# Beepoo.net
KiCad netlist of a schematic drawn in EAGLE
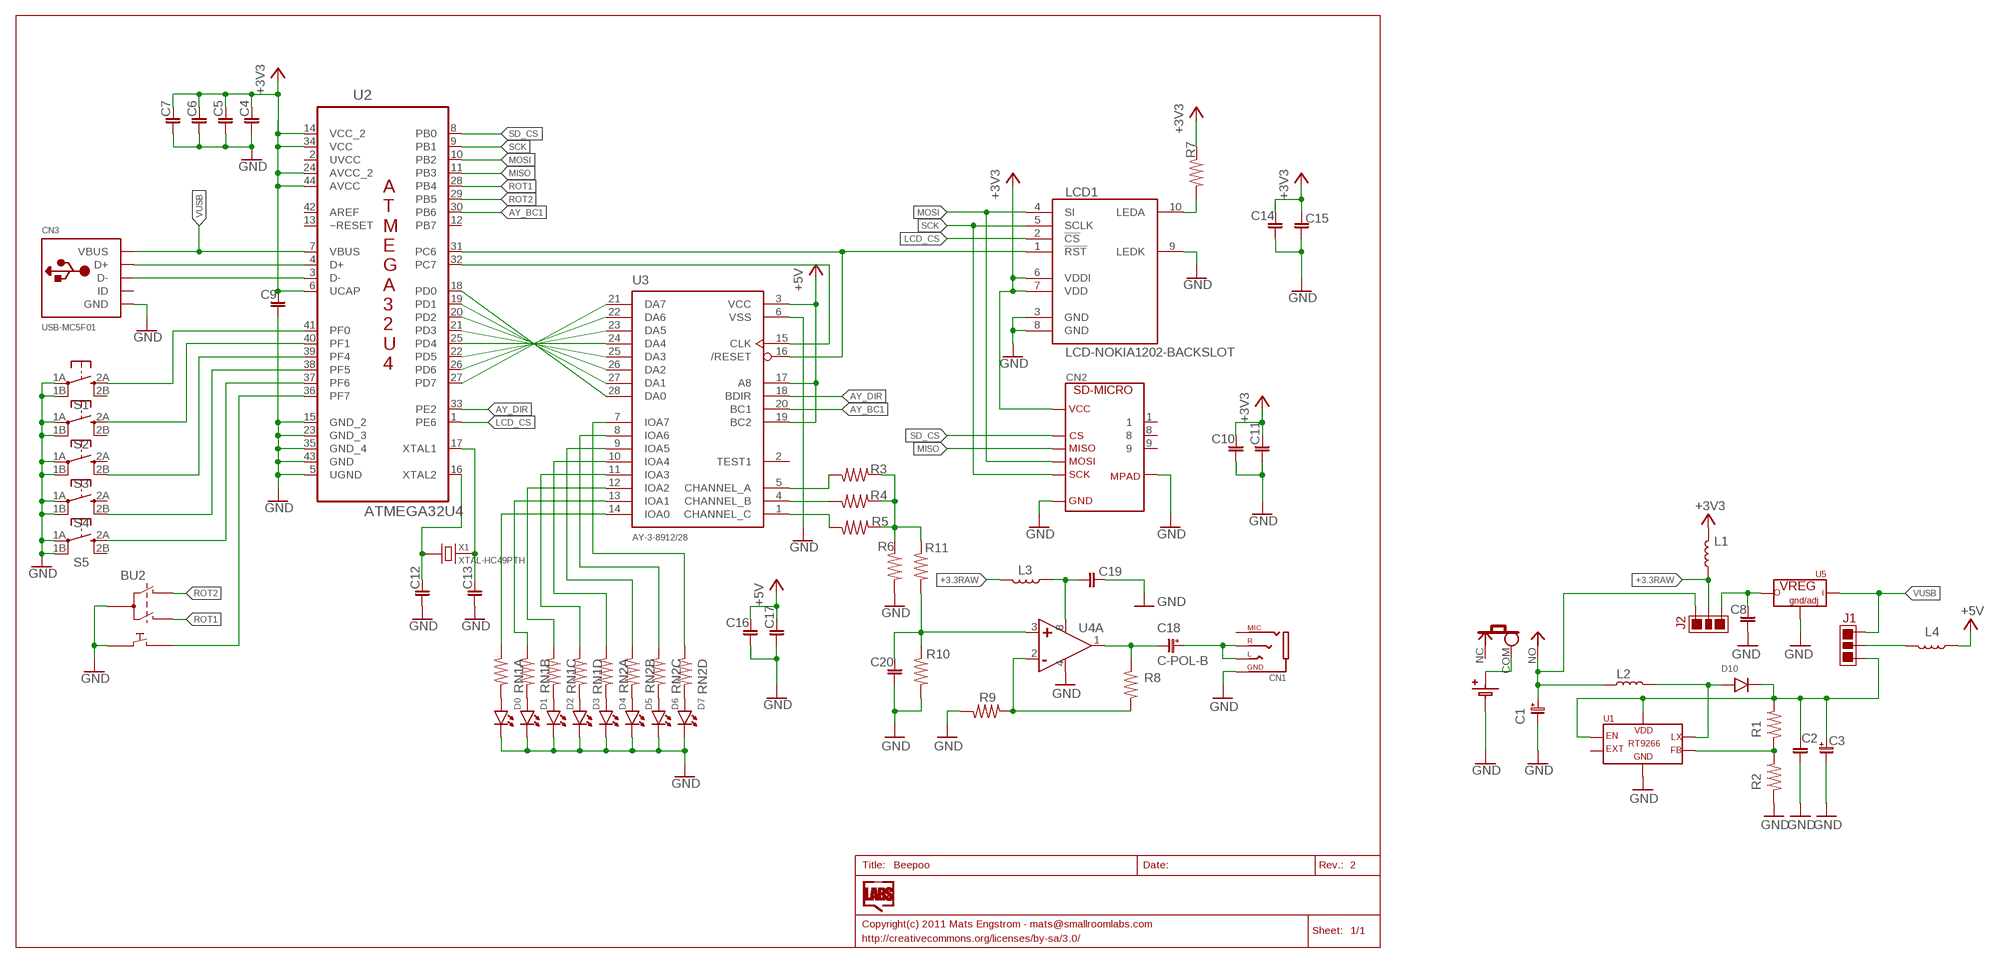
[diagram p0: schematic, sheet 1]

(export (version "E")
  (design (tool "Eeschema 10.0.6"))
  (components
    (comp (ref "BA1")
      (value "BATTERY2-CR123")
      (footprint "eagle-import:BAT-CR123A")
      (libsource (lib "eagle-import") (part "BATTERY2-CR123"))
    )
    (comp (ref "BU2")
      (value "ROTARY")
      (footprint "eagle-import:ROTARY")
      (libsource (lib "eagle-import") (part "ROTARY"))
    )
    (comp (ref "C1")
      (value "C-POL-C")
      (footprint "eagle-import:PANASONIC_C")
      (libsource (lib "eagle-import") (part "C-POL-C"))
    )
    (comp (ref "C2")
      (value "C-0805")
      (footprint "eagle-import:C0805")
      (libsource (lib "eagle-import") (part "C-0805"))
    )
    (comp (ref "C3")
      (value "EEEFK0J101UR")
      (footprint "eagle-import:PANASONIC_C")
      (libsource (lib "eagle-import") (part "C-POL-C"))
    )
    (comp (ref "C4")
      (value "C-0805")
      (footprint "eagle-import:C0805")
      (libsource (lib "eagle-import") (part "C-0805"))
    )
    (comp (ref "C5")
      (value "C-0805")
      (footprint "eagle-import:C0805")
      (libsource (lib "eagle-import") (part "C-0805"))
    )
    (comp (ref "C6")
      (value "C-0805")
      (footprint "eagle-import:C0805")
      (libsource (lib "eagle-import") (part "C-0805"))
    )
    (comp (ref "C7")
      (value "C-0805")
      (footprint "eagle-import:C0805")
      (libsource (lib "eagle-import") (part "C-0805"))
    )
    (comp (ref "C8")
      (value "1u")
      (footprint "eagle-import:C0805")
      (libsource (lib "eagle-import") (part "C-0805"))
    )
    (comp (ref "C9")
      (value "1u")
      (footprint "eagle-import:C0805")
      (libsource (lib "eagle-import") (part "C-0805"))
    )
    (comp (ref "C10")
      (value "1u")
      (footprint "eagle-import:C0805")
      (libsource (lib "eagle-import") (part "C-0805"))
    )
    (comp (ref "C11")
      (value "C-0805")
      (footprint "eagle-import:C0805")
      (libsource (lib "eagle-import") (part "C-0805"))
    )
    (comp (ref "C12")
      (value "C-0805")
      (footprint "eagle-import:C0805")
      (libsource (lib "eagle-import") (part "C-0805"))
    )
    (comp (ref "C13")
      (value "C-0805")
      (footprint "eagle-import:C0805")
      (libsource (lib "eagle-import") (part "C-0805"))
    )
    (comp (ref "C14")
      (value "1u")
      (footprint "eagle-import:C0805")
      (libsource (lib "eagle-import") (part "C-0805"))
    )
    (comp (ref "C15")
      (value "C-0805")
      (footprint "eagle-import:C0805")
      (libsource (lib "eagle-import") (part "C-0805"))
    )
    (comp (ref "C16")
      (value "1u")
      (footprint "eagle-import:C0805")
      (libsource (lib "eagle-import") (part "C-0805"))
    )
    (comp (ref "C17")
      (value "C-0805")
      (footprint "eagle-import:C0805")
      (libsource (lib "eagle-import") (part "C-0805"))
    )
    (comp (ref "C18")
      (value "C-POL-B")
      (footprint "eagle-import:PANASONIC_B")
      (libsource (lib "eagle-import") (part "C-POL-B"))
    )
    (comp (ref "C19")
      (value "1u")
      (footprint "eagle-import:C0805")
      (libsource (lib "eagle-import") (part "C-0805"))
    )
    (comp (ref "C20")
      (value "C-0805")
      (footprint "eagle-import:C0805")
      (libsource (lib "eagle-import") (part "C-0805"))
    )
    (comp (ref "CN1")
      (value "JACK4PTH")
      (footprint "eagle-import:PJ320E")
      (libsource (lib "eagle-import") (part "JACK4PTH"))
    )
    (comp (ref "CN2")
      (value "SD-MICRO")
      (footprint "eagle-import:SD-TFP09")
      (libsource (lib "eagle-import") (part "SD-MICRO"))
    )
    (comp (ref "CN3")
      (value "USB-MC5F01")
      (footprint "eagle-import:USB-MICRO-MC5F01")
      (libsource (lib "eagle-import") (part "USB-MC5F01"))
    )
    (comp (ref "D0")
      (value "LED-0805")
      (footprint "eagle-import:LED0805")
      (libsource (lib "eagle-import") (part "LED-0805"))
    )
    (comp (ref "D1")
      (value "LED-0805")
      (footprint "eagle-import:LED0805")
      (libsource (lib "eagle-import") (part "LED-0805"))
    )
    (comp (ref "D2")
      (value "LED-0805")
      (footprint "eagle-import:LED0805")
      (libsource (lib "eagle-import") (part "LED-0805"))
    )
    (comp (ref "D3")
      (value "LED-0805")
      (footprint "eagle-import:LED0805")
      (libsource (lib "eagle-import") (part "LED-0805"))
    )
    (comp (ref "D4")
      (value "LED-0805")
      (footprint "eagle-import:LED0805")
      (libsource (lib "eagle-import") (part "LED-0805"))
    )
    (comp (ref "D5")
      (value "LED-0805")
      (footprint "eagle-import:LED0805")
      (libsource (lib "eagle-import") (part "LED-0805"))
    )
    (comp (ref "D6")
      (value "LED-0805")
      (footprint "eagle-import:LED0805")
      (libsource (lib "eagle-import") (part "LED-0805"))
    )
    (comp (ref "D7")
      (value "LED-0805")
      (footprint "eagle-import:LED0805")
      (libsource (lib "eagle-import") (part "LED-0805"))
    )
    (comp (ref "D10")
      (value "DIODE-SOD123")
      (footprint "eagle-import:SOD123")
      (libsource (lib "eagle-import") (part "DIODE-SOD123"))
    )
    (comp (ref "J1")
      (value "JUMPER3-1.5MM")
      (footprint "eagle-import:JP3-1.5MM")
      (libsource (lib "eagle-import") (part "JUMPER3-1.5MM"))
    )
    (comp (ref "J2")
      (value "JUMPER3-1.5MM")
      (footprint "eagle-import:JP3-1.5MM")
      (libsource (lib "eagle-import") (part "JUMPER3-1.5MM"))
    )
    (comp (ref "L1")
      (value "L-0805")
      (footprint "eagle-import:L0805")
      (libsource (lib "eagle-import") (part "L-0805"))
    )
    (comp (ref "L2")
      (value "L-BOURNS-SRP7030")
      (footprint "eagle-import:IND-BOURNS-SRP7030")
      (libsource (lib "eagle-import") (part "L-BOURNS-SRP7030"))
    )
    (comp (ref "L3")
      (value "L-0805")
      (footprint "eagle-import:L0805")
      (libsource (lib "eagle-import") (part "L-0805"))
    )
    (comp (ref "L4")
      (value "L-0805")
      (footprint "eagle-import:L0805")
      (libsource (lib "eagle-import") (part "L-0805"))
    )
    (comp (ref "LCD1")
      (value "LCD-NOKIA1202-BACKSLOT")
      (footprint "eagle-import:NOKIA1202LCD-BACK-SLOT")
      (libsource (lib "eagle-import") (part "LCD-NOKIA1202-BACKSLOT"))
    )
    (comp (ref "R1")
      (value "R-0805")
      (footprint "eagle-import:R0805")
      (libsource (lib "eagle-import") (part "R-0805"))
    )
    (comp (ref "R2")
      (value "R-0805")
      (footprint "eagle-import:R0805")
      (libsource (lib "eagle-import") (part "R-0805"))
    )
    (comp (ref "R3")
      (value "R-0805")
      (footprint "eagle-import:R0805")
      (libsource (lib "eagle-import") (part "R-0805"))
    )
    (comp (ref "R4")
      (value "R-0805")
      (footprint "eagle-import:R0805")
      (libsource (lib "eagle-import") (part "R-0805"))
    )
    (comp (ref "R5")
      (value "R-0805")
      (footprint "eagle-import:R0805")
      (libsource (lib "eagle-import") (part "R-0805"))
    )
    (comp (ref "R6")
      (value "R-0805")
      (footprint "eagle-import:R0805")
      (libsource (lib "eagle-import") (part "R-0805"))
    )
    (comp (ref "R7")
      (value "R-0805")
      (footprint "eagle-import:R0805")
      (libsource (lib "eagle-import") (part "R-0805"))
    )
    (comp (ref "R8")
      (value "R-0805")
      (footprint "eagle-import:R0805")
      (libsource (lib "eagle-import") (part "R-0805"))
    )
    (comp (ref "R9")
      (value "R-0805")
      (footprint "eagle-import:R0805")
      (libsource (lib "eagle-import") (part "R-0805"))
    )
    (comp (ref "R10")
      (value "R-0805")
      (footprint "eagle-import:R0805")
      (libsource (lib "eagle-import") (part "R-0805"))
    )
    (comp (ref "R11")
      (value "R-0805")
      (footprint "eagle-import:R0805")
      (libsource (lib "eagle-import") (part "R-0805"))
    )
    (comp (ref "RN1")
      (value "R-ARR4")
      (footprint "eagle-import:RN8P-4R-CRA06S")
      (libsource (lib "eagle-import") (part "R-ARR4"))
    )
    (comp (ref "RN2")
      (value "R-ARR4")
      (footprint "eagle-import:RN8P-4R-CRA06S")
      (libsource (lib "eagle-import") (part "R-ARR4"))
    )
    (comp (ref "S1")
      (value "SWITCH2-12X12PTH")
      (footprint "eagle-import:TACT12X12-PTH")
      (libsource (lib "eagle-import") (part "SWITCH2-12X12PTH"))
    )
    (comp (ref "S2")
      (value "SWITCH2-12X12PTH")
      (footprint "eagle-import:TACT12X12-PTH")
      (libsource (lib "eagle-import") (part "SWITCH2-12X12PTH"))
    )
    (comp (ref "S3")
      (value "SWITCH2-12X12PTH")
      (footprint "eagle-import:TACT12X12-PTH")
      (libsource (lib "eagle-import") (part "SWITCH2-12X12PTH"))
    )
    (comp (ref "S4")
      (value "SWITCH2-12X12PTH")
      (footprint "eagle-import:TACT12X12-PTH")
      (libsource (lib "eagle-import") (part "SWITCH2-12X12PTH"))
    )
    (comp (ref "S5")
      (value "SWITCH2-12X12PTH")
      (footprint "eagle-import:TACT12X12-PTH")
      (libsource (lib "eagle-import") (part "SWITCH2-12X12PTH"))
    )
    (comp (ref "SW2")
      (value "SLIDE1-PCM12")
      (footprint "eagle-import:SW-PCM12")
      (libsource (lib "eagle-import") (part "SLIDE1-PCM12"))
    )
    (comp (ref "U1")
      (value "RT9266-SOT23")
      (footprint "eagle-import:SOT23-6")
      (libsource (lib "eagle-import") (part "RT9266-SOT23"))
    )
    (comp (ref "U2")
      (value "ATMEGA32U4")
      (footprint "eagle-import:TQFP44")
      (libsource (lib "eagle-import") (part "ATMEGA32U4"))
    )
    (comp (ref "U3")
      (value "AY-3-8912/28")
      (footprint "eagle-import:DIL28-6")
      (libsource (lib "eagle-import") (part "AY-3-8912/28"))
    )
    (comp (ref "U4")
      (value "OPAMP-DUAL-SOIC8")
      (footprint "eagle-import:SO08")
      (libsource (lib "eagle-import") (part "OPAMP-DUAL-SOIC8"))
    )
    (comp (ref "U5")
      (value "VREG3-SOT223")
      (footprint "eagle-import:SOT223")
      (libsource (lib "eagle-import") (part "VREG3-SOT223"))
    )
    (comp (ref "X1")
      (value "XTAL-HC49PTH")
      (footprint "eagle-import:HC49US")
      (libsource (lib "eagle-import") (part "XTAL-HC49PTH"))
    )
  )
  (nets
    (net (code "1") (name "+3.3RAW") (class "Default")
      (node (ref "J2") (pin "P$2") (pinfunction "P$2_P$2") (pintype "bidirectional"))
      (node (ref "L1") (pin "1") (pinfunction "P$1_1") (pintype "bidirectional"))
      (node (ref "L3") (pin "2") (pinfunction "P$2_2") (pintype "bidirectional"))
    )
    (net (code "2") (name "+3V3") (class "Default")
      (node (ref "C10") (pin "2") (pinfunction "P$2_2") (pintype "bidirectional"))
      (node (ref "C11") (pin "2") (pinfunction "P$2_2") (pintype "bidirectional"))
      (node (ref "C14") (pin "2") (pinfunction "P$2_2") (pintype "bidirectional"))
      (node (ref "C15") (pin "2") (pinfunction "P$2_2") (pintype "bidirectional"))
      (node (ref "C4") (pin "2") (pinfunction "P$2_2") (pintype "bidirectional"))
      (node (ref "C5") (pin "2") (pinfunction "P$2_2") (pintype "bidirectional"))
      (node (ref "C6") (pin "2") (pinfunction "P$2_2") (pintype "bidirectional"))
      (node (ref "C7") (pin "2") (pinfunction "P$2_2") (pintype "bidirectional"))
      (node (ref "C9") (pin "2") (pinfunction "P$2_2") (pintype "bidirectional"))
      (node (ref "CN2") (pin "4") (pinfunction "P$4_4") (pintype "power_in"))
      (node (ref "L1") (pin "2") (pinfunction "P$2_2") (pintype "bidirectional"))
      (node (ref "LCD1") (pin "6") (pinfunction "VDDI_6") (pintype "power_in"))
      (node (ref "LCD1") (pin "7") (pinfunction "VDD_7") (pintype "power_in"))
      (node (ref "R7") (pin "1") (pinfunction "P$1_1") (pintype "passive"))
      (node (ref "U2") (pin "14") (pinfunction "VCC_2_14") (pintype "power_in"))
      (node (ref "U2") (pin "24") (pinfunction "AVCC_2_24") (pintype "power_in"))
      (node (ref "U2") (pin "34") (pinfunction "VCC_34") (pintype "power_in"))
      (node (ref "U2") (pin "44") (pinfunction "AVCC_44") (pintype "power_in"))
      (node (ref "U2") (pin "6") (pinfunction "UCAP_6") (pintype "power_in"))
    )
    (net (code "3") (name "+5V") (class "Default")
      (node (ref "C16") (pin "2") (pinfunction "P$2_2") (pintype "bidirectional"))
      (node (ref "C17") (pin "2") (pinfunction "P$2_2") (pintype "bidirectional"))
      (node (ref "L4") (pin "1") (pinfunction "P$1_1") (pintype "bidirectional"))
      (node (ref "U3") (pin "17") (pinfunction "A8_17") (pintype "input"))
      (node (ref "U3") (pin "19") (pinfunction "BC2_19") (pintype "input"))
      (node (ref "U3") (pin "3") (pinfunction "VCC_3") (pintype "power_in"))
    )
    (net (code "4") (name "/UVCC") (class "Default")
      (node (ref "U2") (pin "2") (pinfunction "UVCC_2") (pintype "power_in"))
    )
    (net (code "5") (name "AY_BC1") (class "Default")
      (node (ref "U2") (pin "30") (pinfunction "PB6_30") (pintype "bidirectional"))
      (node (ref "U3") (pin "20") (pinfunction "BC1_20") (pintype "input"))
    )
    (net (code "6") (name "AY_DIR") (class "Default")
      (node (ref "U2") (pin "33") (pinfunction "PE2_33") (pintype "bidirectional"))
      (node (ref "U3") (pin "18") (pinfunction "BDIR_18") (pintype "input"))
    )
    (net (code "7") (name "GND") (class "Default")
      (node (ref "BA1") (pin "NEG") (pinfunction "NEG_NEG") (pintype "power_in"))
      (node (ref "BU2") (pin "Q") (pinfunction "Q_Q") (pintype "bidirectional"))
      (node (ref "BU2") (pin "SW1") (pinfunction "SW1_SW1") (pintype "bidirectional"))
      (node (ref "C1") (pin "-") (pinfunction "C_-") (pintype "bidirectional"))
      (node (ref "C10") (pin "1") (pinfunction "P$1_1") (pintype "bidirectional"))
      (node (ref "C11") (pin "1") (pinfunction "P$1_1") (pintype "bidirectional"))
      (node (ref "C12") (pin "1") (pinfunction "P$1_1") (pintype "bidirectional"))
      (node (ref "C13") (pin "1") (pinfunction "P$1_1") (pintype "bidirectional"))
      (node (ref "C14") (pin "1") (pinfunction "P$1_1") (pintype "bidirectional"))
      (node (ref "C15") (pin "1") (pinfunction "P$1_1") (pintype "bidirectional"))
      (node (ref "C16") (pin "1") (pinfunction "P$1_1") (pintype "bidirectional"))
      (node (ref "C17") (pin "1") (pinfunction "P$1_1") (pintype "bidirectional"))
      (node (ref "C19") (pin "2") (pinfunction "P$2_2") (pintype "bidirectional"))
      (node (ref "C2") (pin "2") (pinfunction "P$2_2") (pintype "bidirectional"))
      (node (ref "C20") (pin "1") (pinfunction "P$1_1") (pintype "bidirectional"))
      (node (ref "C3") (pin "-") (pinfunction "C_-") (pintype "bidirectional"))
      (node (ref "C4") (pin "1") (pinfunction "P$1_1") (pintype "bidirectional"))
      (node (ref "C5") (pin "1") (pinfunction "P$1_1") (pintype "bidirectional"))
      (node (ref "C6") (pin "1") (pinfunction "P$1_1") (pintype "bidirectional"))
      (node (ref "C7") (pin "1") (pinfunction "P$1_1") (pintype "bidirectional"))
      (node (ref "C8") (pin "1") (pinfunction "P$1_1") (pintype "bidirectional"))
      (node (ref "C9") (pin "1") (pinfunction "P$1_1") (pintype "bidirectional"))
      (node (ref "CN1") (pin "G") (pinfunction "GND_G") (pintype "bidirectional"))
      (node (ref "CN2") (pin "GND@1") (pinfunction "P$6_GND@1") (pintype "power_in"))
      (node (ref "CN2") (pin "GND@2") (pinfunction "P$10_GND@2") (pintype "bidirectional"))
      (node (ref "CN3") (pin "P5") (pinfunction "GND_P5") (pintype "power_in"))
      (node (ref "D0") (pin "C") (pinfunction "C_C") (pintype "passive"))
      (node (ref "D1") (pin "C") (pinfunction "C_C") (pintype "passive"))
      (node (ref "D2") (pin "C") (pinfunction "C_C") (pintype "passive"))
      (node (ref "D3") (pin "C") (pinfunction "C_C") (pintype "passive"))
      (node (ref "D4") (pin "C") (pinfunction "C_C") (pintype "passive"))
      (node (ref "D5") (pin "C") (pinfunction "C_C") (pintype "passive"))
      (node (ref "D6") (pin "C") (pinfunction "C_C") (pintype "passive"))
      (node (ref "D7") (pin "C") (pinfunction "C_C") (pintype "passive"))
      (node (ref "LCD1") (pin "3") (pinfunction "GND_3") (pintype "power_in"))
      (node (ref "LCD1") (pin "8") (pinfunction "GND_8") (pintype "power_in"))
      (node (ref "LCD1") (pin "9") (pinfunction "LEDK_9") (pintype "passive"))
      (node (ref "R10") (pin "2") (pinfunction "P$2_2") (pintype "passive"))
      (node (ref "R2") (pin "1") (pinfunction "P$1_1") (pintype "passive"))
      (node (ref "R6") (pin "2") (pinfunction "P$2_2") (pintype "passive"))
      (node (ref "R9") (pin "2") (pinfunction "P$2_2") (pintype "passive"))
      (node (ref "S1") (pin "1A") (pinfunction "1A_1A") (pintype "passive"))
      (node (ref "S1") (pin "1B") (pinfunction "1B_1B") (pintype "passive"))
      (node (ref "S2") (pin "1A") (pinfunction "1A_1A") (pintype "passive"))
      (node (ref "S2") (pin "1B") (pinfunction "1B_1B") (pintype "passive"))
      (node (ref "S3") (pin "1A") (pinfunction "1A_1A") (pintype "passive"))
      (node (ref "S3") (pin "1B") (pinfunction "1B_1B") (pintype "passive"))
      (node (ref "S4") (pin "1A") (pinfunction "1A_1A") (pintype "passive"))
      (node (ref "S4") (pin "1B") (pinfunction "1B_1B") (pintype "passive"))
      (node (ref "S5") (pin "1A") (pinfunction "1A_1A") (pintype "passive"))
      (node (ref "S5") (pin "1B") (pinfunction "1B_1B") (pintype "passive"))
      (node (ref "U1") (pin "3") (pinfunction "GND_3") (pintype "power_in"))
      (node (ref "U2") (pin "15") (pinfunction "GND_2_15") (pintype "passive"))
      (node (ref "U2") (pin "23") (pinfunction "GND_3_23") (pintype "passive"))
      (node (ref "U2") (pin "35") (pinfunction "GND_4_35") (pintype "passive"))
      (node (ref "U2") (pin "43") (pinfunction "GND_43") (pintype "passive"))
      (node (ref "U2") (pin "5") (pinfunction "UGND_5") (pintype "passive"))
      (node (ref "U3") (pin "6") (pinfunction "VSS_6") (pintype "power_in"))
      (node (ref "U4") (pin "4") (pinfunction "V-_4") (pintype "power_in"))
      (node (ref "U5") (pin "1") (pinfunction "G/A_1") (pintype "bidirectional"))
    )
    (net (code "8") (name "LCD_CS") (class "Default")
      (node (ref "LCD1") (pin "2") (pinfunction "~{CS}_2") (pintype "input"))
      (node (ref "U2") (pin "1") (pinfunction "PE6_1") (pintype "bidirectional"))
    )
    (net (code "9") (name "MISO") (class "Default")
      (node (ref "CN2") (pin "7") (pinfunction "P$7_7") (pintype "output"))
      (node (ref "U2") (pin "11") (pinfunction "PB3_11") (pintype "bidirectional"))
    )
    (net (code "10") (name "MOSI") (class "Default")
      (node (ref "CN2") (pin "3") (pinfunction "P$3_3") (pintype "input"))
      (node (ref "LCD1") (pin "4") (pinfunction "SI_4") (pintype "input"))
      (node (ref "U2") (pin "10") (pinfunction "PB2_10") (pintype "bidirectional"))
    )
    (net (code "11") (name "Net-(BA1-POS1)") (class "Default")
      (node (ref "BA1") (pin "POS") (pinfunction "POS1_POS") (pintype "power_in"))
      (node (ref "SW2") (pin "COM") (pinfunction "COM_COM") (pintype "bidirectional"))
    )
    (net (code "12") (name "Net-(C1-A)") (class "Default")
      (node (ref "C1") (pin "+") (pinfunction "A_+") (pintype "bidirectional"))
      (node (ref "J2") (pin "P$1") (pinfunction "P$1_P$1") (pintype "bidirectional"))
      (node (ref "L2") (pin "P$1") (pinfunction "P$1_P$1") (pintype "bidirectional"))
      (node (ref "SW2") (pin "NO") (pinfunction "NO_NO") (pintype "bidirectional"))
    )
    (net (code "13") (name "Net-(C2-P$1)") (class "Default")
      (node (ref "C2") (pin "1") (pinfunction "P$1_1") (pintype "bidirectional"))
      (node (ref "C3") (pin "+") (pinfunction "A_+") (pintype "bidirectional"))
      (node (ref "D10") (pin "C") (pinfunction "C_C") (pintype "passive"))
      (node (ref "J1") (pin "P$3") (pinfunction "P$3_P$3") (pintype "bidirectional"))
      (node (ref "R1") (pin "2") (pinfunction "P$2_2") (pintype "passive"))
      (node (ref "U1") (pin "1") (pinfunction "EN_1") (pintype "bidirectional"))
      (node (ref "U1") (pin "5") (pinfunction "VDD_5") (pintype "bidirectional"))
    )
    (net (code "14") (name "Net-(C8-P$2)") (class "Default")
      (node (ref "C8") (pin "2") (pinfunction "P$2_2") (pintype "bidirectional"))
      (node (ref "J2") (pin "P$3") (pinfunction "P$3_P$3") (pintype "bidirectional"))
      (node (ref "U5") (pin "2") (pinfunction "OUT_2") (pintype "bidirectional"))
      (node (ref "U5") (pin "4") (pinfunction "OUT_4") (pintype "bidirectional"))
    )
    (net (code "15") (name "Net-(C12-P$2)") (class "Default")
      (node (ref "C12") (pin "2") (pinfunction "P$2_2") (pintype "bidirectional"))
      (node (ref "U2") (pin "16") (pinfunction "XTAL2_16") (pintype "output"))
      (node (ref "X1") (pin "1") (pinfunction "P$1_1") (pintype "bidirectional"))
    )
    (net (code "16") (name "Net-(C13-P$2)") (class "Default")
      (node (ref "C13") (pin "2") (pinfunction "P$2_2") (pintype "bidirectional"))
      (node (ref "U2") (pin "17") (pinfunction "XTAL1_17") (pintype "input"))
      (node (ref "X1") (pin "2") (pinfunction "P$2_2") (pintype "bidirectional"))
    )
    (net (code "17") (name "Net-(C18-A)") (class "Default")
      (node (ref "C18") (pin "+") (pinfunction "A_+") (pintype "bidirectional"))
      (node (ref "CN1") (pin "L") (pinfunction "L_L") (pintype "bidirectional"))
      (node (ref "CN1") (pin "R") (pinfunction "R_R") (pintype "bidirectional"))
    )
    (net (code "18") (name "Net-(C18-C)") (class "Default")
      (node (ref "C18") (pin "-") (pinfunction "C_-") (pintype "bidirectional"))
      (node (ref "R8") (pin "1") (pinfunction "P$1_1") (pintype "passive"))
      (node (ref "U4") (pin "1") (pinfunction "OUT_1") (pintype "output"))
    )
    (net (code "19") (name "Net-(C19-P$1)") (class "Default")
      (node (ref "C19") (pin "1") (pinfunction "P$1_1") (pintype "bidirectional"))
      (node (ref "L3") (pin "1") (pinfunction "P$1_1") (pintype "bidirectional"))
      (node (ref "U4") (pin "8") (pinfunction "V+_8") (pintype "power_in"))
    )
    (net (code "20") (name "Net-(C20-P$2)") (class "Default")
      (node (ref "C20") (pin "2") (pinfunction "P$2_2") (pintype "bidirectional"))
      (node (ref "R10") (pin "1") (pinfunction "P$1_1") (pintype "passive"))
      (node (ref "R11") (pin "2") (pinfunction "P$2_2") (pintype "passive"))
      (node (ref "U4") (pin "3") (pinfunction "POS_3") (pintype "input"))
    )
    (net (code "21") (name "Net-(CN3-D+)") (class "Default")
      (node (ref "CN3") (pin "P3") (pinfunction "D+_P3") (pintype "bidirectional"))
      (node (ref "U2") (pin "4") (pinfunction "D+_4") (pintype "passive"))
    )
    (net (code "22") (name "Net-(CN3-D-)") (class "Default")
      (node (ref "CN3") (pin "P2") (pinfunction "D-_P2") (pintype "bidirectional"))
      (node (ref "U2") (pin "3") (pinfunction "D-_3") (pintype "passive"))
    )
    (net (code "23") (name "Net-(L4-P$2)") (class "Default")
      (node (ref "J1") (pin "P$2") (pinfunction "P$2_P$2") (pintype "bidirectional"))
      (node (ref "L4") (pin "2") (pinfunction "P$2_2") (pintype "bidirectional"))
    )
    (net (code "24") (name "Net-(LCD1-LEDA)") (class "Default")
      (node (ref "LCD1") (pin "10") (pinfunction "LEDA_10") (pintype "passive"))
      (node (ref "R7") (pin "2") (pinfunction "P$2_2") (pintype "passive"))
    )
    (net (code "25") (name "Net-(LCD1-~{RST})") (class "Default")
      (node (ref "LCD1") (pin "1") (pinfunction "~{RST}_1") (pintype "input"))
      (node (ref "U2") (pin "31") (pinfunction "PC6_31") (pintype "bidirectional"))
      (node (ref "U3") (pin "16") (pinfunction "/RESET_16") (pintype "input"))
    )
    (net (code "26") (name "Net-(R1-P$1)") (class "Default")
      (node (ref "R1") (pin "1") (pinfunction "P$1_1") (pintype "passive"))
      (node (ref "R2") (pin "2") (pinfunction "P$2_2") (pintype "passive"))
      (node (ref "U1") (pin "6") (pinfunction "FB_6") (pintype "bidirectional"))
    )
    (net (code "27") (name "Net-(R3-P$2)") (class "Default")
      (node (ref "R3") (pin "2") (pinfunction "P$2_2") (pintype "passive"))
      (node (ref "U3") (pin "5") (pinfunction "CHANNEL_A_5") (pintype "output"))
    )
    (net (code "28") (name "Net-(R4-P$2)") (class "Default")
      (node (ref "R4") (pin "2") (pinfunction "P$2_2") (pintype "passive"))
      (node (ref "U3") (pin "4") (pinfunction "CHANNEL_B_4") (pintype "output"))
    )
    (net (code "29") (name "Net-(R5-P$2)") (class "Default")
      (node (ref "R5") (pin "2") (pinfunction "P$2_2") (pintype "passive"))
      (node (ref "U3") (pin "1") (pinfunction "CHANNEL_C_1") (pintype "output"))
    )
    (net (code "30") (name "Net-(R8-P$2)") (class "Default")
      (node (ref "R8") (pin "2") (pinfunction "P$2_2") (pintype "passive"))
      (node (ref "R9") (pin "1") (pinfunction "P$1_1") (pintype "passive"))
      (node (ref "U4") (pin "2") (pinfunction "NEG_2") (pintype "input"))
    )
    (net (code "31") (name "Net-(R11-P$1)") (class "Default")
      (node (ref "R11") (pin "1") (pinfunction "P$1_1") (pintype "passive"))
      (node (ref "R3") (pin "1") (pinfunction "P$1_1") (pintype "passive"))
      (node (ref "R4") (pin "1") (pinfunction "P$1_1") (pintype "passive"))
      (node (ref "R5") (pin "1") (pinfunction "P$1_1") (pintype "passive"))
      (node (ref "R6") (pin "1") (pinfunction "P$1_1") (pintype "passive"))
    )
    (net (code "32") (name "Net-(RN1A-P$1)") (class "Default")
      (node (ref "RN1") (pin "1") (pinfunction "P$1_1") (pintype "passive"))
      (node (ref "U3") (pin "14") (pinfunction "IOA0_14") (pintype "bidirectional"))
    )
    (net (code "33") (name "Net-(RN1A-P$2)") (class "Default")
      (node (ref "D0") (pin "A") (pinfunction "A_A") (pintype "passive"))
      (node (ref "RN1") (pin "8") (pinfunction "P$2_8") (pintype "passive"))
    )
    (net (code "34") (name "Net-(RN1B-P$1)") (class "Default")
      (node (ref "RN1") (pin "2") (pinfunction "P$1_2") (pintype "passive"))
      (node (ref "U3") (pin "13") (pinfunction "IOA1_13") (pintype "bidirectional"))
    )
    (net (code "35") (name "Net-(RN1B-P$2)") (class "Default")
      (node (ref "D1") (pin "A") (pinfunction "A_A") (pintype "passive"))
      (node (ref "RN1") (pin "7") (pinfunction "P$2_7") (pintype "passive"))
    )
    (net (code "36") (name "Net-(RN1C-P$1)") (class "Default")
      (node (ref "RN1") (pin "3") (pinfunction "P$1_3") (pintype "passive"))
      (node (ref "U3") (pin "12") (pinfunction "IOA2_12") (pintype "bidirectional"))
    )
    (net (code "37") (name "Net-(RN1C-P$2)") (class "Default")
      (node (ref "D2") (pin "A") (pinfunction "A_A") (pintype "passive"))
      (node (ref "RN1") (pin "6") (pinfunction "P$2_6") (pintype "passive"))
    )
    (net (code "38") (name "Net-(RN1D-P$1)") (class "Default")
      (node (ref "RN1") (pin "4") (pinfunction "P$1_4") (pintype "passive"))
      (node (ref "U3") (pin "11") (pinfunction "IOA3_11") (pintype "bidirectional"))
    )
    (net (code "39") (name "Net-(RN1D-P$2)") (class "Default")
      (node (ref "D3") (pin "A") (pinfunction "A_A") (pintype "passive"))
      (node (ref "RN1") (pin "5") (pinfunction "P$2_5") (pintype "passive"))
    )
    (net (code "40") (name "Net-(RN2A-P$1)") (class "Default")
      (node (ref "RN2") (pin "1") (pinfunction "P$1_1") (pintype "passive"))
      (node (ref "U3") (pin "10") (pinfunction "IOA4_10") (pintype "bidirectional"))
    )
    (net (code "41") (name "Net-(RN2A-P$2)") (class "Default")
      (node (ref "D4") (pin "A") (pinfunction "A_A") (pintype "passive"))
      (node (ref "RN2") (pin "8") (pinfunction "P$2_8") (pintype "passive"))
    )
    (net (code "42") (name "Net-(RN2B-P$1)") (class "Default")
      (node (ref "RN2") (pin "2") (pinfunction "P$1_2") (pintype "passive"))
      (node (ref "U3") (pin "9") (pinfunction "IOA5_9") (pintype "bidirectional"))
    )
    (net (code "43") (name "Net-(RN2B-P$2)") (class "Default")
      (node (ref "D5") (pin "A") (pinfunction "A_A") (pintype "passive"))
      (node (ref "RN2") (pin "7") (pinfunction "P$2_7") (pintype "passive"))
    )
    (net (code "44") (name "Net-(RN2C-P$1)") (class "Default")
      (node (ref "RN2") (pin "3") (pinfunction "P$1_3") (pintype "passive"))
      (node (ref "U3") (pin "8") (pinfunction "IOA6_8") (pintype "bidirectional"))
    )
    (net (code "45") (name "Net-(RN2C-P$2)") (class "Default")
      (node (ref "D6") (pin "A") (pinfunction "A_A") (pintype "passive"))
      (node (ref "RN2") (pin "6") (pinfunction "P$2_6") (pintype "passive"))
    )
    (net (code "46") (name "Net-(RN2D-P$1)") (class "Default")
      (node (ref "RN2") (pin "4") (pinfunction "P$1_4") (pintype "passive"))
      (node (ref "U3") (pin "7") (pinfunction "IOA7_7") (pintype "bidirectional"))
    )
    (net (code "47") (name "Net-(RN2D-P$2)") (class "Default")
      (node (ref "D7") (pin "A") (pinfunction "A_A") (pintype "passive"))
      (node (ref "RN2") (pin "5") (pinfunction "P$2_5") (pintype "passive"))
    )
    (net (code "48") (name "Net-(U1-LX)") (class "Default")
      (node (ref "D10") (pin "A") (pinfunction "A_A") (pintype "passive"))
      (node (ref "L2") (pin "P$2") (pinfunction "P$2_P$2") (pintype "bidirectional"))
      (node (ref "U1") (pin "4") (pinfunction "LX_4") (pintype "bidirectional"))
    )
    (net (code "49") (name "Net-(U2-PC7)") (class "Default")
      (node (ref "U2") (pin "32") (pinfunction "PC7_32") (pintype "bidirectional"))
      (node (ref "U3") (pin "15") (pinfunction "CLK_15") (pintype "input"))
    )
    (net (code "50") (name "Net-(U2-PD0)") (class "Default")
      (node (ref "U2") (pin "18") (pinfunction "PD0_18") (pintype "bidirectional"))
      (node (ref "U3") (pin "28") (pinfunction "DA0_28") (pintype "bidirectional"))
    )
    (net (code "51") (name "Net-(U2-PD1)") (class "Default")
      (node (ref "U2") (pin "19") (pinfunction "PD1_19") (pintype "bidirectional"))
      (node (ref "U3") (pin "27") (pinfunction "DA1_27") (pintype "bidirectional"))
    )
    (net (code "52") (name "Net-(U2-PD2)") (class "Default")
      (node (ref "U2") (pin "20") (pinfunction "PD2_20") (pintype "bidirectional"))
      (node (ref "U3") (pin "26") (pinfunction "DA2_26") (pintype "bidirectional"))
    )
    (net (code "53") (name "Net-(U2-PD3)") (class "Default")
      (node (ref "U2") (pin "21") (pinfunction "PD3_21") (pintype "bidirectional"))
      (node (ref "U3") (pin "25") (pinfunction "DA3_25") (pintype "bidirectional"))
    )
    (net (code "54") (name "Net-(U2-PD4)") (class "Default")
      (node (ref "U2") (pin "25") (pinfunction "PD4_25") (pintype "bidirectional"))
      (node (ref "U3") (pin "24") (pinfunction "DA4_24") (pintype "bidirectional"))
    )
    (net (code "55") (name "Net-(U2-PD5)") (class "Default")
      (node (ref "U2") (pin "22") (pinfunction "PD5_22") (pintype "bidirectional"))
      (node (ref "U3") (pin "23") (pinfunction "DA5_23") (pintype "bidirectional"))
    )
    (net (code "56") (name "Net-(U2-PD6)") (class "Default")
      (node (ref "U2") (pin "26") (pinfunction "PD6_26") (pintype "bidirectional"))
      (node (ref "U3") (pin "22") (pinfunction "DA6_22") (pintype "bidirectional"))
    )
    (net (code "57") (name "Net-(U2-PD7)") (class "Default")
      (node (ref "U2") (pin "27") (pinfunction "PD7_27") (pintype "bidirectional"))
      (node (ref "U3") (pin "21") (pinfunction "DA7_21") (pintype "bidirectional"))
    )
    (net (code "58") (name "Net-(U2-PF0)") (class "Default")
      (node (ref "S1") (pin "2A") (pinfunction "2A_2A") (pintype "passive"))
      (node (ref "U2") (pin "41") (pinfunction "PF0_41") (pintype "bidirectional"))
    )
    (net (code "59") (name "Net-(U2-PF1)") (class "Default")
      (node (ref "S2") (pin "2A") (pinfunction "2A_2A") (pintype "passive"))
      (node (ref "U2") (pin "40") (pinfunction "PF1_40") (pintype "bidirectional"))
    )
    (net (code "60") (name "Net-(U2-PF4)") (class "Default")
      (node (ref "S3") (pin "2B") (pinfunction "2B_2B") (pintype "passive"))
      (node (ref "U2") (pin "39") (pinfunction "PF4_39") (pintype "bidirectional"))
    )
    (net (code "61") (name "Net-(U2-PF5)") (class "Default")
      (node (ref "S4") (pin "2B") (pinfunction "2B_2B") (pintype "passive"))
      (node (ref "U2") (pin "38") (pinfunction "PF5_38") (pintype "bidirectional"))
    )
    (net (code "62") (name "Net-(U2-PF6)") (class "Default")
      (node (ref "S5") (pin "2A") (pinfunction "2A_2A") (pintype "passive"))
      (node (ref "U2") (pin "37") (pinfunction "PF6_37") (pintype "bidirectional"))
    )
    (net (code "63") (name "Net-(U2-PF7)") (class "Default")
      (node (ref "BU2") (pin "SW2") (pinfunction "SW2_SW2") (pintype "bidirectional"))
      (node (ref "U2") (pin "36") (pinfunction "PF7_36") (pintype "bidirectional"))
    )
    (net (code "64") (name "ROT1") (class "Default")
      (node (ref "BU2") (pin "Q2") (pinfunction "Q2_Q2") (pintype "bidirectional"))
      (node (ref "U2") (pin "28") (pinfunction "PB4_28") (pintype "bidirectional"))
    )
    (net (code "65") (name "ROT2") (class "Default")
      (node (ref "BU2") (pin "Q1") (pinfunction "Q1_Q1") (pintype "bidirectional"))
      (node (ref "U2") (pin "29") (pinfunction "PB5_29") (pintype "bidirectional"))
    )
    (net (code "66") (name "SCK") (class "Default")
      (node (ref "CN2") (pin "5") (pinfunction "P$5_5") (pintype "input"))
      (node (ref "LCD1") (pin "5") (pinfunction "SCLK_5") (pintype "input"))
      (node (ref "U2") (pin "9") (pinfunction "PB1_9") (pintype "bidirectional"))
    )
    (net (code "67") (name "SD_CS") (class "Default")
      (node (ref "CN2") (pin "2") (pinfunction "P$2_2") (pintype "input"))
      (node (ref "U2") (pin "8") (pinfunction "PB0_8") (pintype "bidirectional"))
    )
    (net (code "68") (name "VUSB") (class "Default")
      (node (ref "CN3") (pin "P1") (pinfunction "VBUS_P1") (pintype "power_in"))
      (node (ref "J1") (pin "P$1") (pinfunction "P$1_P$1") (pintype "bidirectional"))
      (node (ref "U2") (pin "7") (pinfunction "VBUS_7") (pintype "input"))
      (node (ref "U5") (pin "3") (pinfunction "IN_3") (pintype "bidirectional"))
    )
    (net (code "69") (name "unconnected-(CN1-PadMIC)") (class "Default")
      (node (ref "CN1") (pin "MIC") (pinfunction "MIC_MIC") (pintype "bidirectional"))
    )
    (net (code "70") (name "unconnected-(CN2-Pad1)") (class "Default")
      (node (ref "CN2") (pin "1") (pinfunction "1_1") (pintype "no_connect"))
    )
    (net (code "71") (name "unconnected-(CN2-Pad8)") (class "Default")
      (node (ref "CN2") (pin "8") (pinfunction "8_8") (pintype "no_connect"))
    )
    (net (code "72") (name "unconnected-(CN2-Pad9)") (class "Default")
      (node (ref "CN2") (pin "9") (pinfunction "9_9") (pintype "no_connect"))
    )
    (net (code "73") (name "unconnected-(CN3-ID-PadP4)") (class "Default")
      (node (ref "CN3") (pin "P4") (pinfunction "ID_P4") (pintype "bidirectional"))
    )
    (net (code "74") (name "unconnected-(S1-Pad2B)") (class "Default")
      (node (ref "S1") (pin "2B") (pinfunction "2B_2B") (pintype "passive"))
    )
    (net (code "75") (name "unconnected-(S2-Pad2B)") (class "Default")
      (node (ref "S2") (pin "2B") (pinfunction "2B_2B") (pintype "passive"))
    )
    (net (code "76") (name "unconnected-(S3-Pad2A)") (class "Default")
      (node (ref "S3") (pin "2A") (pinfunction "2A_2A") (pintype "passive"))
    )
    (net (code "77") (name "unconnected-(S4-Pad2A)") (class "Default")
      (node (ref "S4") (pin "2A") (pinfunction "2A_2A") (pintype "passive"))
    )
    (net (code "78") (name "unconnected-(S5-Pad2B)") (class "Default")
      (node (ref "S5") (pin "2B") (pinfunction "2B_2B") (pintype "passive"))
    )
    (net (code "79") (name "unconnected-(SW2-PadNC)") (class "Default")
      (node (ref "SW2") (pin "NC") (pinfunction "NC_NC") (pintype "bidirectional"))
    )
    (net (code "80") (name "unconnected-(U1-EXT-Pad2)") (class "Default")
      (node (ref "U1") (pin "2") (pinfunction "EXT_2") (pintype "bidirectional"))
    )
    (net (code "81") (name "unconnected-(U2-AREF-Pad42)") (class "Default")
      (node (ref "U2") (pin "42") (pinfunction "AREF_42") (pintype "input"))
    )
    (net (code "82") (name "unconnected-(U2-PB7-Pad12)") (class "Default")
      (node (ref "U2") (pin "12") (pinfunction "PB7_12") (pintype "bidirectional"))
    )
    (net (code "83") (name "unconnected-(U2-~{RESET}-Pad13)") (class "Default")
      (node (ref "U2") (pin "13") (pinfunction "~{RESET}_13") (pintype "input"))
    )
    (net (code "84") (name "unconnected-(U3-TEST1-Pad2)") (class "Default")
      (node (ref "U3") (pin "2") (pinfunction "TEST1_2") (pintype "no_connect"))
    )
  )
)
